# HV_Sense.net
KiCad netlist of a schematic drawn in Altium Designer
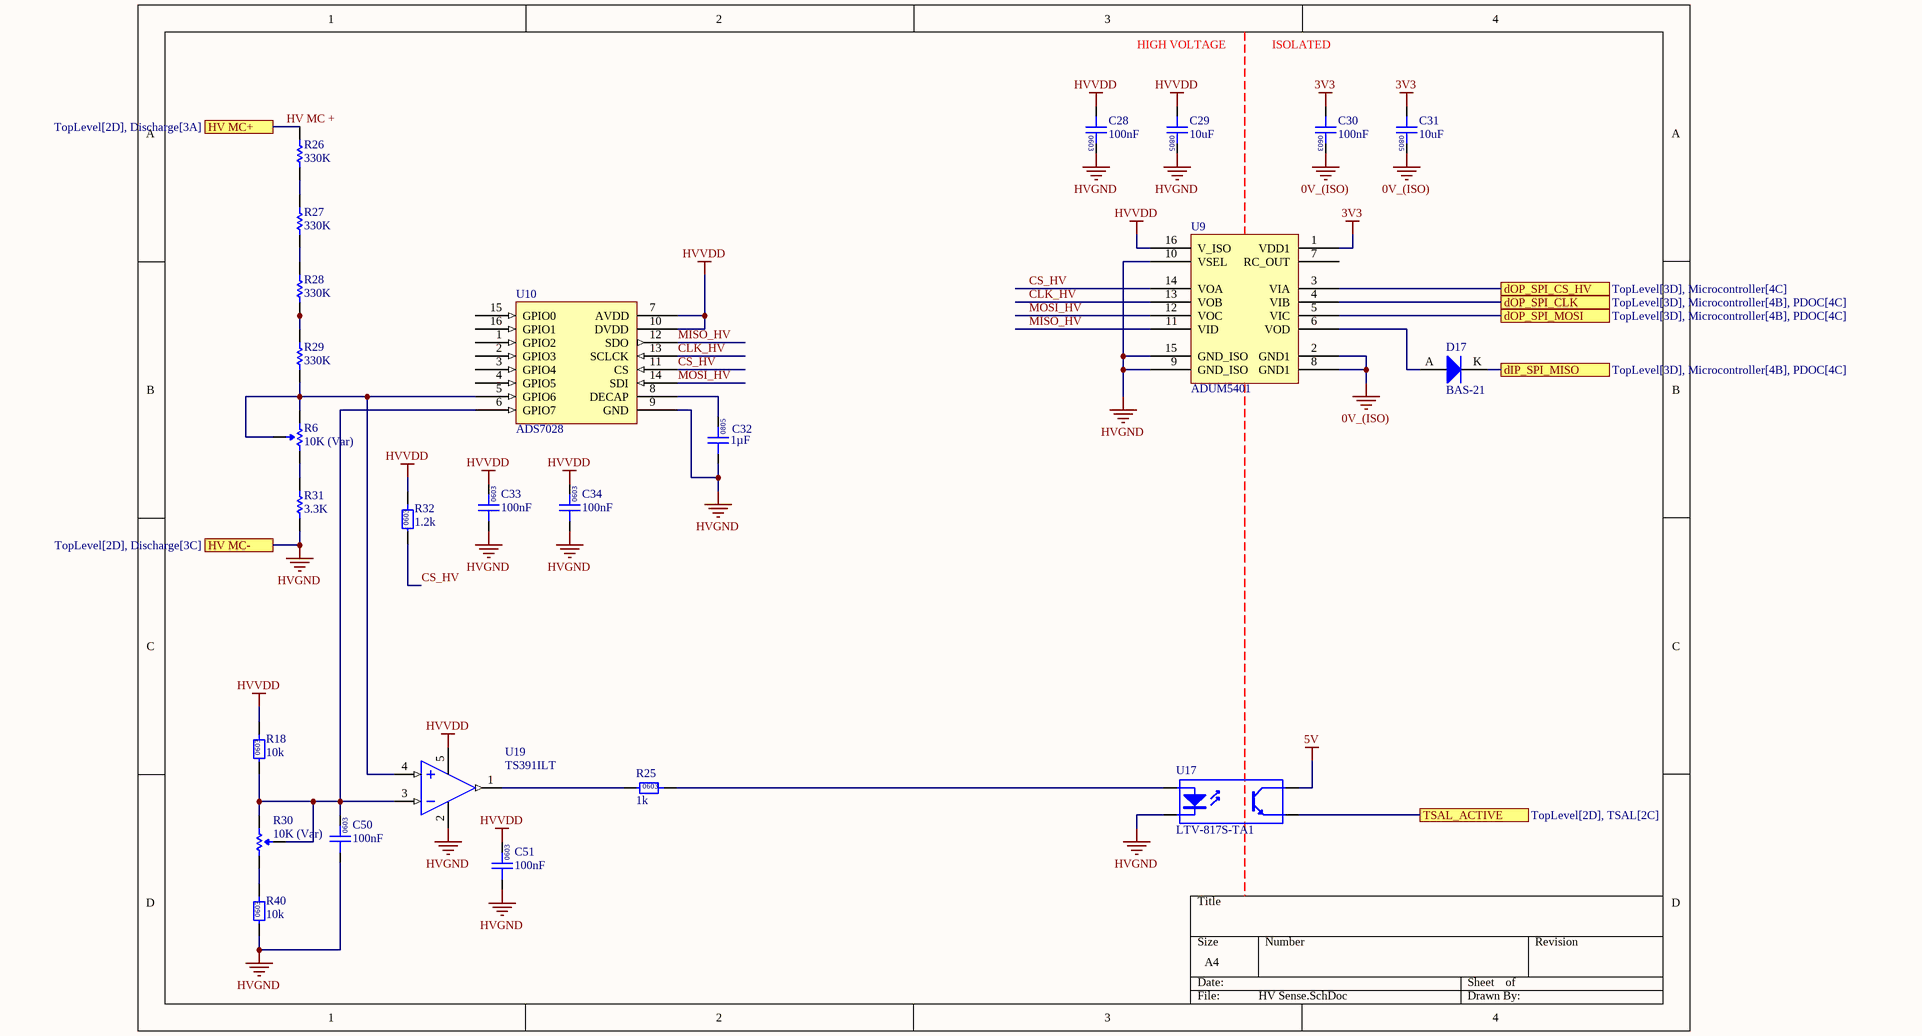
[diagram p0: HV Sense.SchDoc]

(export (version "E")
  (design (tool "Eeschema 10.0.6"))
  (components
    (comp (ref "C28")
      (value "100nF")
      (footprint "0603")
      (fields
        (field (name "PART NUMBER") "GCM188L81H104KA57D")
        (field (name "MANUFACTURER") "muRata")
        (field (name "TOLERANCE") "±10%")
      )
      (libsource (lib "ts_standard_library") (part "Capacitor 0603"))
    )
    (comp (ref "C29")
      (value "10uF")
      (footprint "0805")
      (fields
        (field (name "PART NUMBER") "GRM21BR6YA106KE43L")
        (field (name "MANUFACTURER") "muRata")
        (field (name "TOLERANCE") "10%")
      )
      (libsource (lib "ts_standard_library") (part "Capacitor 0805"))
    )
    (comp (ref "C30")
      (value "100nF")
      (footprint "0603")
      (fields
        (field (name "PART NUMBER") "GCM188L81H104KA57D")
        (field (name "MANUFACTURER") "muRata")
        (field (name "TOLERANCE") "±10%")
      )
      (libsource (lib "ts_standard_library") (part "Capacitor 0603"))
    )
    (comp (ref "C31")
      (value "10uF")
      (footprint "0805")
      (fields
        (field (name "PART NUMBER") "GRM21BR6YA106KE43L")
        (field (name "MANUFACTURER") "muRata")
        (field (name "TOLERANCE") "10%")
      )
      (libsource (lib "ts_standard_library") (part "Capacitor 0805"))
    )
    (comp (ref "C32")
      (value "1µF")
      (footprint "0805")
      (fields
        (field (name "PART NUMBER") "GCM21BR71H105KA03L")
        (field (name "MANUFACTURER") "muRata")
        (field (name "TOLERANCE") "±10%")
      )
      (libsource (lib "ts_standard_library") (part "Capacitor 0805"))
    )
    (comp (ref "C33")
      (value "100nF")
      (footprint "0603")
      (fields
        (field (name "PART NUMBER") "GCM188L81H104KA57D")
        (field (name "MANUFACTURER") "muRata")
        (field (name "TOLERANCE") "±10%")
      )
      (libsource (lib "ts_standard_library") (part "Capacitor 0603"))
    )
    (comp (ref "C34")
      (value "100nF")
      (footprint "0603")
      (fields
        (field (name "PART NUMBER") "GCM188L81H104KA57D")
        (field (name "MANUFACTURER") "muRata")
        (field (name "TOLERANCE") "±10%")
      )
      (libsource (lib "ts_standard_library") (part "Capacitor 0603"))
    )
    (comp (ref "C50")
      (value "100nF")
      (footprint "0603")
      (fields
        (field (name "PART NUMBER") "GCM188L81H104KA57D")
        (field (name "MANUFACTURER") "muRata")
        (field (name "TOLERANCE") "±10%")
      )
      (libsource (lib "ts_standard_library") (part "Capacitor 0603"))
    )
    (comp (ref "C51")
      (value "100nF")
      (footprint "0603")
      (fields
        (field (name "PART NUMBER") "GCM188L81H104KA57D")
        (field (name "MANUFACTURER") "muRata")
        (field (name "TOLERANCE") "±10%")
      )
      (libsource (lib "ts_standard_library") (part "Capacitor 0603"))
    )
    (comp (ref "D17")
      (value "BAS-21")
      (footprint "NEXPERIA_SOT23")
      (fields (field (name "MANUFACTURER") "Nexperia USA Inc."))
      (libsource (lib "ts_standard_library") (part "Diode"))
    )
    (comp (ref "R6")
      (value "10K (Var)")
      (footprint "B 3296")
      (fields
        (field (name "PART NUMBER") "3296W-1-103LF")
        (field (name "MANUFACTURER") "Bournes Inc")
        (field (name "TOLERANCE") "0.1")
      )
      (libsource (lib "ts_standard_library") (part "Resistor (Potentiometer)"))
    )
    (comp (ref "R18")
      (value "10k")
      (footprint "0603")
      (fields
        (field (name "PART NUMBER") "RC0603FR-0710KL")
        (field (name "MANUFACTURER") "YAGEO")
        (field (name "TOLERANCE") "0.01")
      )
      (libsource (lib "ts_standard_library") (part "Resistor 0603"))
    )
    (comp (ref "R25")
      (value "1k")
      (footprint "0603")
      (fields
        (field (name "PART NUMBER") "RC0603FR-071KL")
        (field (name "MANUFACTURER") "YAGEO")
        (field (name "TOLERANCE") "0.01")
      )
      (libsource (lib "ts_standard_library") (part "Resistor 0603"))
    )
    (comp (ref "R26")
      (value "330K")
      (footprint "VB 0207")
      (fields
        (field (name "PART NUMBER") "MMB02070C3303FB200")
        (field (name "MANUFACTURER") "Vishay Beyschlag")
        (field (name "TOLERANCE") "0.01")
      )
      (libsource (lib "ts_standard_library") (part "Resistor"))
    )
    (comp (ref "R27")
      (value "330K")
      (footprint "VB 0207")
      (fields
        (field (name "PART NUMBER") "MMB02070C3303FB200")
        (field (name "MANUFACTURER") "Vishay Beyschlag")
        (field (name "TOLERANCE") "0.01")
      )
      (libsource (lib "ts_standard_library") (part "Resistor"))
    )
    (comp (ref "R28")
      (value "330K")
      (footprint "VB 0207")
      (fields
        (field (name "PART NUMBER") "MMB02070C3303FB200")
        (field (name "MANUFACTURER") "Vishay Beyschlag")
        (field (name "TOLERANCE") "0.01")
      )
      (libsource (lib "ts_standard_library") (part "Resistor"))
    )
    (comp (ref "R29")
      (value "330K")
      (footprint "VB 0207")
      (fields
        (field (name "PART NUMBER") "MMB02070C3303FB200")
        (field (name "MANUFACTURER") "Vishay Beyschlag")
        (field (name "TOLERANCE") "0.01")
      )
      (libsource (lib "ts_standard_library") (part "Resistor"))
    )
    (comp (ref "R30")
      (value "10K (Var)")
      (footprint "B 3296")
      (fields
        (field (name "PART NUMBER") "3296W-1-103LF")
        (field (name "MANUFACTURER") "Bournes Inc")
        (field (name "TOLERANCE") "0.1")
      )
      (libsource (lib "ts_standard_library") (part "Resistor (Potentiometer)"))
    )
    (comp (ref "R31")
      (value "3.3K")
      (footprint "VB 0207")
      (fields
        (field (name "PART NUMBER") "MMB02070C3301FB200")
        (field (name "MANUFACTURER") "Vishay Beyschlag")
        (field (name "TOLERANCE") "0.01")
      )
      (libsource (lib "ts_20-standard-library") (part "Resistor"))
    )
    (comp (ref "R32")
      (value "1.2k")
      (footprint "0603")
      (fields
        (field (name "PART NUMBER") "RC0603JR-071K2L")
        (field (name "MANUFACTURER") "YAGEO")
        (field (name "TOLERANCE") "0.01")
      )
      (libsource (lib "ts_standard_library") (part "Resistor 0603"))
    )
    (comp (ref "R40")
      (value "10k")
      (footprint "0603")
      (fields
        (field (name "PART NUMBER") "RC0603FR-0710KL")
        (field (name "MANUFACTURER") "YAGEO")
        (field (name "TOLERANCE") "0.01")
      )
      (libsource (lib "ts_standard_library") (part "Resistor 0603"))
    )
    (comp (ref "U9")
      (value "ADUM5401")
      (footprint "AD 16-SOIC")
      (description "Quad Channel 2.5kV Digital Isolator with isoPower")
      (fields (field (name "MANUFACTURER") "Analogue Devices"))
      (libsource (lib "ts_standard_library") (part "ADUM5401"))
    )
    (comp (ref "U10")
      (value "ADS7028")
      (footprint "WFQN-16")
      (description "IC ADC 12BIT SAR 16WQFN")
      (fields (field (name "PART NUMBER") "ADS7028IRTER") (field (name "MANUFACTURER") "Texas Instruments"))
      (libsource (lib "ts_standard_library") (part "ADS7028IRTER"))
    )
    (comp (ref "U17")
      (value "LTV-817S-TA1")
      (footprint "ON 4-SMD")
      (description "35V 50ma Optocoupler (VF=1.2V)")
      (fields
        (field (name "MANUFACTURER") "Lite-On Inc")
        (field (name "DIGIKEY PART NUMBER") "160-1893-2-ND")
      )
      (libsource (lib "ts_20-standard-library") (part "LTV-817S-TA1"))
    )
    (comp (ref "U19")
      (value "TS391ILT")
      (footprint "ON SOT-23-5")
      (description "IC COMP LO PWR SGL V SOT 23-5L")
      (libsource (lib "Team Swinburne") (part "TS391ILT"))
    )
  )
  (nets
    (net (code "1") (name "/CLK_HV") (class "Default")
      (node (ref "U10") (pin "13") (pinfunction "SCLCK_13") (pintype "input"))
      (node (ref "U9") (pin "13") (pinfunction "VOB_13") (pintype "passive"))
    )
    (net (code "2") (name "/CS_HV") (class "Default")
      (node (ref "R32") (pin "1") (pinfunction "1_1") (pintype "passive"))
      (node (ref "U10") (pin "11") (pinfunction "CS_11") (pintype "input"))
      (node (ref "U9") (pin "14") (pinfunction "VOA_14") (pintype "passive"))
    )
    (net (code "3") (name "/HV MC +") (class "Default")
      (node (ref "R26") (pin "2") (pinfunction "2_2") (pintype "passive"))
    )
    (net (code "4") (name "/MISO_HV") (class "Default")
      (node (ref "U10") (pin "12") (pinfunction "SDO_12") (pintype "output"))
      (node (ref "U9") (pin "11") (pinfunction "VID_11") (pintype "passive"))
    )
    (net (code "5") (name "/MOSI_HV") (class "Default")
      (node (ref "U10") (pin "14") (pinfunction "SDI_14") (pintype "input"))
      (node (ref "U9") (pin "12") (pinfunction "VOC_12") (pintype "passive"))
    )
    (net (code "6") (name "/TSAL_ACTIVE") (class "Default")
      (node (ref "U17") (pin "3") (pinfunction "E_3") (pintype "passive"))
    )
    (net (code "7") (name "/dIP_SPI_MISO") (class "Default")
      (node (ref "D17") (pin "K") (pinfunction "K_K") (pintype "passive"))
    )
    (net (code "8") (name "/dOP_SPI_CLK") (class "Default")
      (node (ref "U9") (pin "4") (pinfunction "VIB_4") (pintype "passive"))
    )
    (net (code "9") (name "/dOP_SPI_CS_HV") (class "Default")
      (node (ref "U9") (pin "3") (pinfunction "VIA_3") (pintype "passive"))
    )
    (net (code "10") (name "/dOP_SPI_MOSI") (class "Default")
      (node (ref "U9") (pin "5") (pinfunction "VIC_5") (pintype "passive"))
    )
    (net (code "11") (name "0V_(ISO)") (class "Default")
      (node (ref "C30") (pin "2") (pinfunction "2_2") (pintype "passive"))
      (node (ref "C31") (pin "2") (pinfunction "2_2") (pintype "passive"))
      (node (ref "U9") (pin "2") (pinfunction "GND1_2") (pintype "passive"))
      (node (ref "U9") (pin "8") (pinfunction "GND1_8") (pintype "passive"))
    )
    (net (code "12") (name "3V3") (class "Default")
      (node (ref "C30") (pin "1") (pinfunction "1_1") (pintype "passive"))
      (node (ref "C31") (pin "1") (pinfunction "1_1") (pintype "passive"))
      (node (ref "U9") (pin "1") (pinfunction "VDD1_1") (pintype "passive"))
    )
    (net (code "13") (name "5V") (class "Default")
      (node (ref "U17") (pin "4") (pinfunction "C_4") (pintype "passive"))
    )
    (net (code "14") (name "HVGND") (class "Default")
      (node (ref "C28") (pin "2") (pinfunction "2_2") (pintype "passive"))
      (node (ref "C29") (pin "2") (pinfunction "2_2") (pintype "passive"))
      (node (ref "C32") (pin "1") (pinfunction "1_1") (pintype "passive"))
      (node (ref "C33") (pin "1") (pinfunction "1_1") (pintype "passive"))
      (node (ref "C34") (pin "1") (pinfunction "1_1") (pintype "passive"))
      (node (ref "C50") (pin "1") (pinfunction "1_1") (pintype "passive"))
      (node (ref "C51") (pin "1") (pinfunction "1_1") (pintype "passive"))
      (node (ref "R31") (pin "1") (pinfunction "1_1") (pintype "passive"))
      (node (ref "R40") (pin "1") (pinfunction "1_1") (pintype "passive"))
      (node (ref "U10") (pin "9") (pinfunction "GND_9") (pintype "power_in"))
      (node (ref "U17") (pin "2") (pinfunction "K_2") (pintype "passive"))
      (node (ref "U19") (pin "2") (pinfunction "VCC-_2") (pintype "power_in"))
      (node (ref "U9") (pin "10") (pinfunction "VSEL_10") (pintype "passive"))
      (node (ref "U9") (pin "15") (pinfunction "GND_ISO_15") (pintype "passive"))
      (node (ref "U9") (pin "9") (pinfunction "GND_ISO_9") (pintype "passive"))
    )
    (net (code "15") (name "HVVDD") (class "Default")
      (node (ref "C28") (pin "1") (pinfunction "1_1") (pintype "passive"))
      (node (ref "C29") (pin "1") (pinfunction "1_1") (pintype "passive"))
      (node (ref "C33") (pin "2") (pinfunction "2_2") (pintype "passive"))
      (node (ref "C34") (pin "2") (pinfunction "2_2") (pintype "passive"))
      (node (ref "C51") (pin "2") (pinfunction "2_2") (pintype "passive"))
      (node (ref "R18") (pin "2") (pinfunction "2_2") (pintype "passive"))
      (node (ref "R32") (pin "2") (pinfunction "2_2") (pintype "passive"))
      (node (ref "U10") (pin "10") (pinfunction "DVDD_10") (pintype "power_in"))
      (node (ref "U10") (pin "7") (pinfunction "AVDD_7") (pintype "power_in"))
      (node (ref "U19") (pin "5") (pinfunction "VCC+_5") (pintype "power_in"))
      (node (ref "U9") (pin "16") (pinfunction "V_ISO_16") (pintype "passive"))
    )
    (net (code "16") (name "Net-(R6-CCW)") (class "Default")
      (node (ref "R31") (pin "2") (pinfunction "2_2") (pintype "passive"))
      (node (ref "R6") (pin "1") (pinfunction "CCW_1") (pintype "passive"))
    )
    (net (code "17") (name "Net-(R6-CW)") (class "Default")
      (node (ref "R29") (pin "1") (pinfunction "1_1") (pintype "passive"))
      (node (ref "R6") (pin "2") (pinfunction "Wiper_2") (pintype "passive"))
      (node (ref "R6") (pin "3") (pinfunction "CW_3") (pintype "passive"))
      (node (ref "U10") (pin "5") (pinfunction "GPIO6_5") (pintype "input"))
      (node (ref "U19") (pin "4") (pinfunction "IIN+_4") (pintype "input"))
    )
    (net (code "18") (name "Net-(R26-Pad1)") (class "Default")
      (node (ref "R26") (pin "1") (pinfunction "1_1") (pintype "passive"))
      (node (ref "R27") (pin "2") (pinfunction "2_2") (pintype "passive"))
    )
    (net (code "19") (name "Net-(R27-Pad1)") (class "Default")
      (node (ref "R27") (pin "1") (pinfunction "1_1") (pintype "passive"))
      (node (ref "R28") (pin "2") (pinfunction "2_2") (pintype "passive"))
    )
    (net (code "20") (name "Net-(R28-Pad1)") (class "Default")
      (node (ref "R28") (pin "1") (pinfunction "1_1") (pintype "passive"))
      (node (ref "R29") (pin "2") (pinfunction "2_2") (pintype "passive"))
    )
    (net (code "21") (name "Net-(R30-CCW)") (class "Default")
      (node (ref "C50") (pin "2") (pinfunction "2_2") (pintype "passive"))
      (node (ref "R18") (pin "1") (pinfunction "1_1") (pintype "passive"))
      (node (ref "R30") (pin "1") (pinfunction "CCW_1") (pintype "passive"))
      (node (ref "R30") (pin "2") (pinfunction "Wiper_2") (pintype "passive"))
      (node (ref "U10") (pin "6") (pinfunction "GPIO7_6") (pintype "input"))
      (node (ref "U19") (pin "3") (pinfunction "IN-_3") (pintype "input"))
    )
    (net (code "22") (name "Net-(R30-CW)") (class "Default")
      (node (ref "R30") (pin "3") (pinfunction "CW_3") (pintype "passive"))
      (node (ref "R40") (pin "2") (pinfunction "2_2") (pintype "passive"))
    )
    (net (code "23") (name "Net-(U9-VOD)") (class "Default")
      (node (ref "D17") (pin "A") (pinfunction "A_A") (pintype "passive"))
      (node (ref "U9") (pin "6") (pinfunction "VOD_6") (pintype "passive"))
    )
    (net (code "24") (name "Net-(U10-DECAP)") (class "Default")
      (node (ref "C32") (pin "2") (pinfunction "2_2") (pintype "passive"))
      (node (ref "U10") (pin "8") (pinfunction "DECAP_8") (pintype "power_in"))
    )
    (net (code "25") (name "Net-(U17-A)") (class "Default")
      (node (ref "R25") (pin "2") (pinfunction "2_2") (pintype "passive"))
      (node (ref "U17") (pin "1") (pinfunction "A_1") (pintype "passive"))
    )
    (net (code "26") (name "Net-(U19-OUT)") (class "Default")
      (node (ref "R25") (pin "1") (pinfunction "1_1") (pintype "passive"))
      (node (ref "U19") (pin "1") (pinfunction "OUT_1") (pintype "output"))
    )
    (net (code "27") (name "unconnected-(U9-RC_OUT-Pad7)") (class "Default")
      (node (ref "U9") (pin "7") (pinfunction "RC_OUT_7") (pintype "passive"))
    )
    (net (code "28") (name "unconnected-(U10-GPIO0-Pad15)") (class "Default")
      (node (ref "U10") (pin "15") (pinfunction "GPIO0_15") (pintype "input"))
    )
    (net (code "29") (name "unconnected-(U10-GPIO1-Pad16)") (class "Default")
      (node (ref "U10") (pin "16") (pinfunction "GPIO1_16") (pintype "input"))
    )
    (net (code "30") (name "unconnected-(U10-GPIO2-Pad1)") (class "Default")
      (node (ref "U10") (pin "1") (pinfunction "GPIO2_1") (pintype "input"))
    )
    (net (code "31") (name "unconnected-(U10-GPIO3-Pad2)") (class "Default")
      (node (ref "U10") (pin "2") (pinfunction "GPIO3_2") (pintype "input"))
    )
    (net (code "32") (name "unconnected-(U10-GPIO4-Pad3)") (class "Default")
      (node (ref "U10") (pin "3") (pinfunction "GPIO4_3") (pintype "input"))
    )
    (net (code "33") (name "unconnected-(U10-GPIO5-Pad4)") (class "Default")
      (node (ref "U10") (pin "4") (pinfunction "GPIO5_4") (pintype "input"))
    )
  )
)
